# Fan_12V_LED.net
KiCad netlist of a schematic drawn in EasyEDA Pro
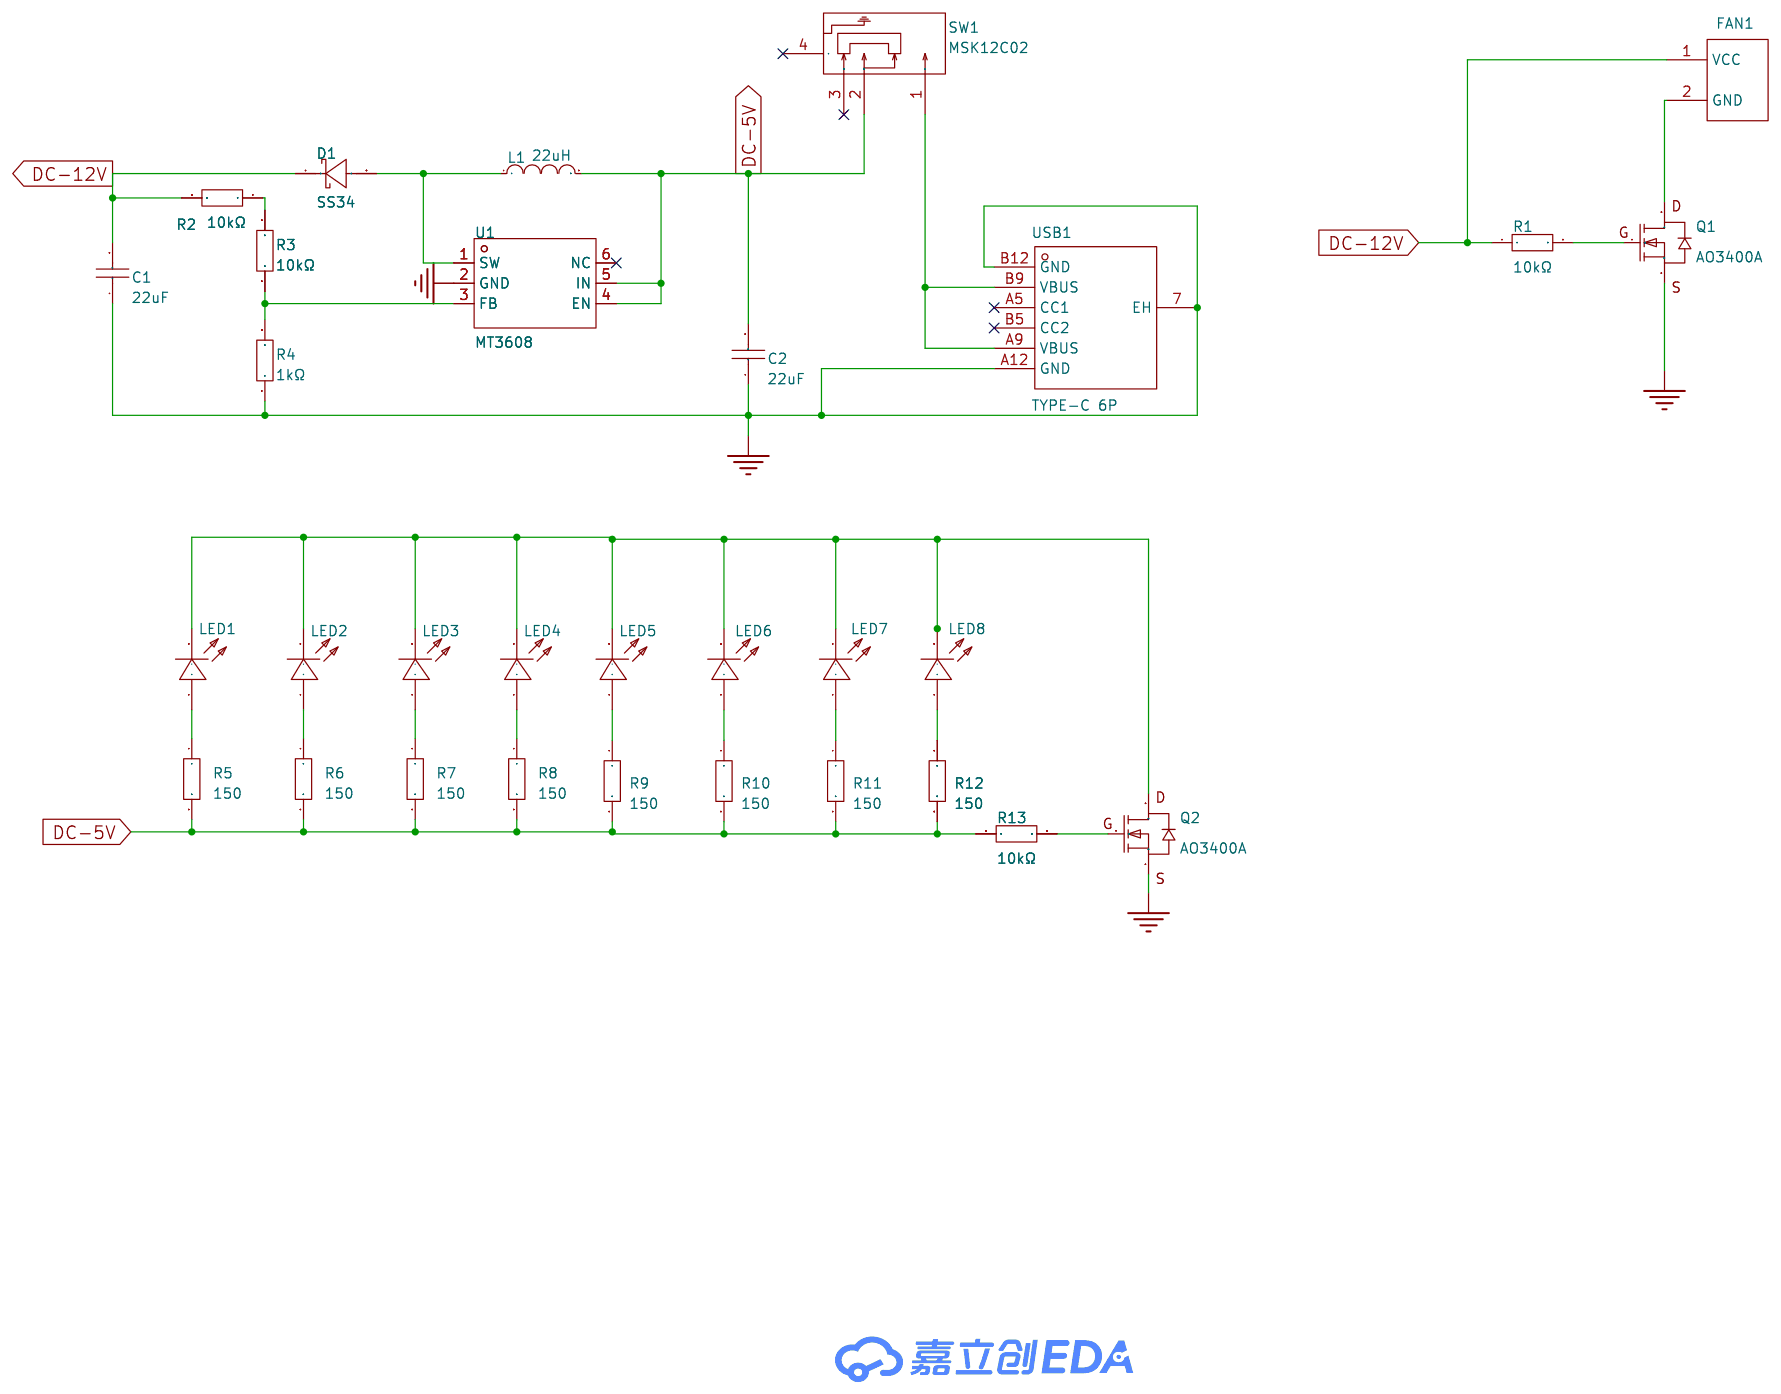
[diagram p0: schematic sheet]

(export (version "E")
  (design (tool "Eeschema 10.0.6"))
  (components
    (comp (ref "C1")
      (value "22uF")
      (footprint "easyedapro:C0603")
      (description "容值:22uF;精度:±20%;额定电压:6.3V;材质(温度系数):X5R;")
      (fields
        (field (name "Manufacturer Part") "CC0603MRX5R5BB226")
        (field (name "Manufacturer") "YAGEO(国巨)")
      )
      (libsource (lib "easyedapro") (part "CC0603MRX5R5BB226"))
    )
    (comp (ref "C2")
      (value "22uF")
      (footprint "easyedapro:C0603")
      (description "容值:22uF;精度:±20%;额定电压:6.3V;材质(温度系数):X5R;")
      (fields
        (field (name "Manufacturer Part") "CC0603MRX5R5BB226")
        (field (name "Manufacturer") "YAGEO(国巨)")
      )
      (libsource (lib "easyedapro") (part "CC0603MRX5R5BB226"))
    )
    (comp (ref "D1")
      (value "SS34")
      (footprint "easyedapro:SMA_L4.2-W2.7-LS5.0-RD")
      (description "二极管配置:-;正向压降(Vf):550mV@3A;直流反向耐压(Vr):40V;整流电流:3A;")
      (fields (field (name "Manufacturer") "JSMSEMI(杰盛微)"))
      (libsource (lib "easyedapro") (part "SS34_C2837271"))
    )
    (comp (ref "FAN1")
      (value "~")
      (footprint "easyedapro:锂电池焊盘封装")
      (libsource (lib "easyedapro") (part "锂电池焊盘"))
    )
    (comp (ref "L1")
      (value "22uH")
      (footprint "easyedapro:IND-SMD_L7.0-W6.6_FXL0630")
      (description "电感值:22uH;精度:±20%;额定电流:2.5A;饱和电流(Isat):3A;类型:一体成型电感;")
      (fields (field (name "Manufacturer Part") "FXL0630-220-M") (field (name "Manufacturer") "cjiang(长江微电)"))
      (libsource (lib "easyedapro") (part "FXL0630-220-M"))
    )
    (comp (ref "LED1")
      (value "NCD0805R1")
      (footprint "easyedapro:LED0805-R-RD")
      (fields (field (name "Manufacturer") "国星光电"))
      (libsource (lib "easyedapro") (part "FC-2012HRK-620D"))
    )
    (comp (ref "LED2")
      (value "NCD0805R1")
      (footprint "easyedapro:LED0805-R-RD")
      (fields (field (name "Manufacturer") "国星光电"))
      (libsource (lib "easyedapro") (part "FC-2012HRK-620D"))
    )
    (comp (ref "LED3")
      (value "NCD0805R1")
      (footprint "easyedapro:LED0805-R-RD")
      (fields (field (name "Manufacturer") "国星光电"))
      (libsource (lib "easyedapro") (part "FC-2012HRK-620D"))
    )
    (comp (ref "LED4")
      (value "NCD0805R1")
      (footprint "easyedapro:LED0805-R-RD")
      (fields (field (name "Manufacturer") "国星光电"))
      (libsource (lib "easyedapro") (part "FC-2012HRK-620D"))
    )
    (comp (ref "LED5")
      (value "NCD0805R1")
      (footprint "easyedapro:LED0805-R-RD")
      (fields (field (name "Manufacturer") "国星光电"))
      (libsource (lib "easyedapro") (part "FC-2012HRK-620D"))
    )
    (comp (ref "LED6")
      (value "NCD0805R1")
      (footprint "easyedapro:LED0805-R-RD")
      (fields (field (name "Manufacturer") "国星光电"))
      (libsource (lib "easyedapro") (part "FC-2012HRK-620D"))
    )
    (comp (ref "LED7")
      (value "NCD0805R1")
      (footprint "easyedapro:LED0805-R-RD")
      (fields (field (name "Manufacturer") "国星光电"))
      (libsource (lib "easyedapro") (part "FC-2012HRK-620D"))
    )
    (comp (ref "LED8")
      (value "NCD0805R1")
      (footprint "easyedapro:LED0805-R-RD")
      (fields (field (name "Manufacturer") "国星光电"))
      (libsource (lib "easyedapro") (part "FC-2012HRK-620D"))
    )
    (comp (ref "Q1")
      (value "AO3400A")
      (footprint "easyedapro:SOT-23-3_L2.9-W1.3-P1.90-LS2.4-BR")
      (fields (field (name "Manufacturer") "UMW(友台半导体)"))
      (libsource (lib "easyedapro") (part "AO3400A_C347475"))
    )
    (comp (ref "Q2")
      (value "AO3400A")
      (footprint "easyedapro:SOT-23-3_L2.9-W1.3-P1.90-LS2.4-BR")
      (fields (field (name "Manufacturer") "UMW(友台半导体)"))
      (libsource (lib "easyedapro") (part "AO3400A_C347475"))
    )
    (comp (ref "R1")
      (value "10kΩ")
      (footprint "easyedapro:R0603")
      (description "电阻类型:厚膜电阻;阻值:10kΩ;精度:±1%;功率:100mW;最大工作电压:75V;温度系数:±100ppm/°C;")
      (fields (field (name "Manufacturer Part") "RC0603FR-0710KL") (field (name "Manufacturer") "YAGEO(国巨)"))
      (libsource (lib "easyedapro") (part "RC0603FR-0710KL"))
    )
    (comp (ref "R2")
      (value "10kΩ")
      (fields (field (name "Manufacturer Part") "RC0603FR-0710KL") (field (name "Manufacturer") "YAGEO(国巨)"))
      (libsource (lib "easyedapro") (part "RC0603FR-0716KL"))
    )
    (comp (ref "R3")
      (value "10kΩ")
      (fields (field (name "Manufacturer Part") "RC0603FR-0710KL") (field (name "Manufacturer") "YAGEO(国巨)"))
      (libsource (lib "easyedapro") (part "RC0603FR-0716KL"))
    )
    (comp (ref "R4")
      (value "1kΩ")
      (fields (field (name "Manufacturer Part") "RC0603FR-071KL") (field (name "Manufacturer") "YAGEO(国巨)"))
      (libsource (lib "easyedapro") (part "RC0603FR-072K2L"))
    )
    (comp (ref "R5")
      (value "150")
      (footprint "easyedapro:R0603")
      (description "电阻类型:厚膜电阻;阻值:100kΩ;精度:±1%;功率:100mW;最大工作电压:75V;温度系数:±100ppm/°C;")
      (fields
        (field (name "Manufacturer Part") "0603WAF1003T5E")
        (field (name "Manufacturer") "UNI-ROYAL(厚声)")
      )
      (libsource (lib "easyedapro") (part "0603WAF1003T5E"))
    )
    (comp (ref "R6")
      (value "150")
      (footprint "easyedapro:R0603")
      (description "电阻类型:厚膜电阻;阻值:100kΩ;精度:±1%;功率:100mW;最大工作电压:75V;温度系数:±100ppm/°C;")
      (fields
        (field (name "Manufacturer Part") "0603WAF1003T5E")
        (field (name "Manufacturer") "UNI-ROYAL(厚声)")
      )
      (libsource (lib "easyedapro") (part "0603WAF1003T5E"))
    )
    (comp (ref "R7")
      (value "150")
      (footprint "easyedapro:R0603")
      (description "电阻类型:厚膜电阻;阻值:100kΩ;精度:±1%;功率:100mW;最大工作电压:75V;温度系数:±100ppm/°C;")
      (fields
        (field (name "Manufacturer Part") "0603WAF1003T5E")
        (field (name "Manufacturer") "UNI-ROYAL(厚声)")
      )
      (libsource (lib "easyedapro") (part "0603WAF1003T5E"))
    )
    (comp (ref "R8")
      (value "150")
      (footprint "easyedapro:R0603")
      (description "电阻类型:厚膜电阻;阻值:100kΩ;精度:±1%;功率:100mW;最大工作电压:75V;温度系数:±100ppm/°C;")
      (fields
        (field (name "Manufacturer Part") "0603WAF1003T5E")
        (field (name "Manufacturer") "UNI-ROYAL(厚声)")
      )
      (libsource (lib "easyedapro") (part "0603WAF1003T5E"))
    )
    (comp (ref "R9")
      (value "150")
      (footprint "easyedapro:R0603")
      (description "电阻类型:厚膜电阻;阻值:100kΩ;精度:±1%;功率:100mW;最大工作电压:75V;温度系数:±100ppm/°C;")
      (fields
        (field (name "Manufacturer Part") "0603WAF1003T5E")
        (field (name "Manufacturer") "UNI-ROYAL(厚声)")
      )
      (libsource (lib "easyedapro") (part "0603WAF1003T5E"))
    )
    (comp (ref "R10")
      (value "150")
      (footprint "easyedapro:R0603")
      (description "电阻类型:厚膜电阻;阻值:100kΩ;精度:±1%;功率:100mW;最大工作电压:75V;温度系数:±100ppm/°C;")
      (fields
        (field (name "Manufacturer Part") "0603WAF1003T5E")
        (field (name "Manufacturer") "UNI-ROYAL(厚声)")
      )
      (libsource (lib "easyedapro") (part "0603WAF1003T5E"))
    )
    (comp (ref "R11")
      (value "150")
      (footprint "easyedapro:R0603")
      (description "电阻类型:厚膜电阻;阻值:100kΩ;精度:±1%;功率:100mW;最大工作电压:75V;温度系数:±100ppm/°C;")
      (fields
        (field (name "Manufacturer Part") "0603WAF1003T5E")
        (field (name "Manufacturer") "UNI-ROYAL(厚声)")
      )
      (libsource (lib "easyedapro") (part "0603WAF1003T5E"))
    )
    (comp (ref "R12")
      (value "150")
      (footprint "easyedapro:R0603")
      (description "电阻类型:厚膜电阻;阻值:100kΩ;精度:±1%;功率:100mW;最大工作电压:75V;温度系数:±100ppm/°C;")
      (fields
        (field (name "Manufacturer Part") "0603WAF1003T5E")
        (field (name "Manufacturer") "UNI-ROYAL(厚声)")
      )
      (libsource (lib "easyedapro") (part "0603WAF1003T5E"))
    )
    (comp (ref "R13")
      (value "10kΩ")
      (footprint "easyedapro:R0603")
      (description "电阻类型:厚膜电阻;阻值:10kΩ;精度:±1%;功率:100mW;最大工作电压:75V;温度系数:±100ppm/°C;")
      (fields (field (name "Manufacturer Part") "RC0603FR-0710KL") (field (name "Manufacturer") "YAGEO(国巨)"))
      (libsource (lib "easyedapro") (part "RC0603FR-0710KL"))
    )
    (comp (ref "SW1")
      (value "MSK12C02")
      (footprint "easyedapro:SW-TH_MSK12C02")
      (description "电路结构:单刀双掷;安装方式:卧贴;开关颜色:-;额定电流(DC):50mA;额定电压(DC):12V;额定电流(AC):-;额定电压(AC):-;机械寿命:1万次;")
      (fields (field (name "Manufacturer") "SHOU HAN(首韩)"))
      (libsource (lib "easyedapro") (part "MSK12C02"))
    )
    (comp (ref "U1")
      (value "MT3608")
      (footprint "easyedapro:SOT-23-6_L2.9-W1.6-P0.95-LS2.8-BL")
      (description "功能类型:升压型;输出类型:可调;工作电压:2V~24V;输出电压:28V;输出电流:2A;")
      (fields (field (name "Manufacturer") "西安航天民芯"))
      (libsource (lib "easyedapro") (part "MT3608"))
    )
    (comp (ref "USB1")
      (value "TYPE-C 6P")
      (footprint "easyedapro:TYPE-C-SMD_TYPE-C-6P")
      (description "连接器类型:Type-C;标准:USB 3.1;公母:母;安装方式:卧贴;触点数量:6P;端口数量:1;额定电流 - 电源:5A;工作温度范围:-40°C~+85°C;")
      (fields (field (name "Manufacturer") "SHOU HAN(首韩)"))
      (libsource (lib "easyedapro") (part "TYPE-C 6P"))
    )
  )
  (nets
    (net (code "1") (name "DC-5V") (class "Default")
      (node (ref "C2") (pin "2") (pinfunction "2_2") (pintype "input"))
      (node (ref "L1") (pin "2") (pinfunction "2_2") (pintype "unspecified"))
      (node (ref "R10") (pin "2") (pinfunction "2_2") (pintype "input"))
      (node (ref "R11") (pin "2") (pinfunction "2_2") (pintype "input"))
      (node (ref "R12") (pin "2") (pinfunction "2_2") (pintype "input"))
      (node (ref "R13") (pin "1") (pinfunction "1_1") (pintype "input"))
      (node (ref "R5") (pin "2") (pinfunction "2_2") (pintype "input"))
      (node (ref "R6") (pin "2") (pinfunction "2_2") (pintype "input"))
      (node (ref "R7") (pin "2") (pinfunction "2_2") (pintype "input"))
      (node (ref "R8") (pin "2") (pinfunction "2_2") (pintype "input"))
      (node (ref "R9") (pin "2") (pinfunction "2_2") (pintype "input"))
      (node (ref "SW1") (pin "2") (pinfunction "2_2") (pintype "unspecified"))
      (node (ref "U1") (pin "4") (pinfunction "EN_4") (pintype "unspecified"))
      (node (ref "U1") (pin "5") (pinfunction "IN_5") (pintype "unspecified"))
    )
    (net (code "2") (name "DC-12V") (class "Default")
      (node (ref "C1") (pin "2") (pinfunction "2_2") (pintype "input"))
      (node (ref "D1") (pin "1") (pinfunction "K_1") (pintype "unspecified"))
      (node (ref "FAN1") (pin "1") (pinfunction "VCC_1") (pintype "input"))
      (node (ref "R1") (pin "1") (pinfunction "1_1") (pintype "input"))
      (node (ref "R2") (pin "2") (pinfunction "2_2") (pintype "input"))
    )
    (net (code "3") (name "GND") (class "Default")
      (node (ref "C1") (pin "1") (pinfunction "1_1") (pintype "input"))
      (node (ref "C2") (pin "1") (pinfunction "1_1") (pintype "input"))
      (node (ref "Q1") (pin "2") (pinfunction "S_2") (pintype "unspecified"))
      (node (ref "Q2") (pin "2") (pinfunction "S_2") (pintype "unspecified"))
      (node (ref "R4") (pin "1") (pinfunction "1_1") (pintype "input"))
      (node (ref "U1") (pin "2") (pinfunction "GND_2") (pintype "unspecified"))
      (node (ref "USB1") (pin "7") (pinfunction "EH_7") (pintype "unspecified"))
      (node (ref "USB1") (pin "A12") (pinfunction "GND_A12") (pintype "unspecified"))
      (node (ref "USB1") (pin "B12") (pinfunction "GND_B12") (pintype "unspecified"))
    )
    (net (code "4") (name "Net-(D1-A)") (class "Default")
      (node (ref "D1") (pin "2") (pinfunction "A_2") (pintype "unspecified"))
      (node (ref "L1") (pin "1") (pinfunction "1_1") (pintype "unspecified"))
      (node (ref "U1") (pin "1") (pinfunction "SW_1") (pintype "unspecified"))
    )
    (net (code "5") (name "Net-(FAN1-GND)") (class "Default")
      (node (ref "FAN1") (pin "2") (pinfunction "GND_2") (pintype "input"))
      (node (ref "Q1") (pin "3") (pinfunction "D_3") (pintype "unspecified"))
    )
    (net (code "6") (name "Net-(LED1-+)") (class "Default")
      (node (ref "LED1") (pin "1") (pinfunction "+_1") (pintype "unspecified"))
      (node (ref "R5") (pin "1") (pinfunction "1_1") (pintype "input"))
    )
    (net (code "7") (name "Net-(LED1--)") (class "Default")
      (node (ref "LED1") (pin "2") (pinfunction "-_2") (pintype "unspecified"))
      (node (ref "LED2") (pin "2") (pinfunction "-_2") (pintype "unspecified"))
      (node (ref "LED3") (pin "2") (pinfunction "-_2") (pintype "unspecified"))
      (node (ref "LED4") (pin "2") (pinfunction "-_2") (pintype "unspecified"))
      (node (ref "LED5") (pin "2") (pinfunction "-_2") (pintype "unspecified"))
      (node (ref "LED6") (pin "2") (pinfunction "-_2") (pintype "unspecified"))
      (node (ref "LED7") (pin "2") (pinfunction "-_2") (pintype "unspecified"))
      (node (ref "LED8") (pin "2") (pinfunction "-_2") (pintype "unspecified"))
      (node (ref "Q2") (pin "3") (pinfunction "D_3") (pintype "unspecified"))
    )
    (net (code "8") (name "Net-(LED2-+)") (class "Default")
      (node (ref "LED2") (pin "1") (pinfunction "+_1") (pintype "unspecified"))
      (node (ref "R6") (pin "1") (pinfunction "1_1") (pintype "input"))
    )
    (net (code "9") (name "Net-(LED3-+)") (class "Default")
      (node (ref "LED3") (pin "1") (pinfunction "+_1") (pintype "unspecified"))
      (node (ref "R7") (pin "1") (pinfunction "1_1") (pintype "input"))
    )
    (net (code "10") (name "Net-(LED4-+)") (class "Default")
      (node (ref "LED4") (pin "1") (pinfunction "+_1") (pintype "unspecified"))
      (node (ref "R8") (pin "1") (pinfunction "1_1") (pintype "input"))
    )
    (net (code "11") (name "Net-(LED5-+)") (class "Default")
      (node (ref "LED5") (pin "1") (pinfunction "+_1") (pintype "unspecified"))
      (node (ref "R9") (pin "1") (pinfunction "1_1") (pintype "input"))
    )
    (net (code "12") (name "Net-(LED6-+)") (class "Default")
      (node (ref "LED6") (pin "1") (pinfunction "+_1") (pintype "unspecified"))
      (node (ref "R10") (pin "1") (pinfunction "1_1") (pintype "input"))
    )
    (net (code "13") (name "Net-(LED7-+)") (class "Default")
      (node (ref "LED7") (pin "1") (pinfunction "+_1") (pintype "unspecified"))
      (node (ref "R11") (pin "1") (pinfunction "1_1") (pintype "input"))
    )
    (net (code "14") (name "Net-(LED8-+)") (class "Default")
      (node (ref "LED8") (pin "1") (pinfunction "+_1") (pintype "unspecified"))
      (node (ref "R12") (pin "1") (pinfunction "1_1") (pintype "input"))
    )
    (net (code "15") (name "Net-(Q1-G)") (class "Default")
      (node (ref "Q1") (pin "1") (pinfunction "G_1") (pintype "unspecified"))
      (node (ref "R1") (pin "2") (pinfunction "2_2") (pintype "input"))
    )
    (net (code "16") (name "Net-(Q2-G)") (class "Default")
      (node (ref "Q2") (pin "1") (pinfunction "G_1") (pintype "unspecified"))
      (node (ref "R13") (pin "2") (pinfunction "2_2") (pintype "input"))
    )
    (net (code "17") (name "Net-(R2-Pad1)") (class "Default")
      (node (ref "R2") (pin "1") (pinfunction "1_1") (pintype "input"))
      (node (ref "R3") (pin "2") (pinfunction "2_2") (pintype "input"))
    )
    (net (code "18") (name "Net-(SW1-Pad1)") (class "Default")
      (node (ref "SW1") (pin "1") (pinfunction "1_1") (pintype "unspecified"))
      (node (ref "USB1") (pin "A9") (pinfunction "VBUS_A9") (pintype "unspecified"))
      (node (ref "USB1") (pin "B9") (pinfunction "VBUS_B9") (pintype "unspecified"))
    )
    (net (code "19") (name "Net-(U1-FB)") (class "Default")
      (node (ref "R3") (pin "1") (pinfunction "1_1") (pintype "input"))
      (node (ref "R4") (pin "2") (pinfunction "2_2") (pintype "input"))
      (node (ref "U1") (pin "3") (pinfunction "FB_3") (pintype "unspecified"))
    )
    (net (code "20") (name "unconnected-(SW1-Pad3)") (class "Default")
      (node (ref "SW1") (pin "3") (pinfunction "3_3") (pintype "unspecified+no_connect"))
    )
    (net (code "21") (name "unconnected-(SW1-Pad4)") (class "Default")
      (node (ref "SW1") (pin "4") (pinfunction "4_4") (pintype "unspecified+no_connect"))
    )
    (net (code "22") (name "unconnected-(U1-NC-Pad6)") (class "Default")
      (node (ref "U1") (pin "6") (pinfunction "NC_6") (pintype "unspecified+no_connect"))
    )
    (net (code "23") (name "unconnected-(USB1-CC1-PadA5)") (class "Default")
      (node (ref "USB1") (pin "A5") (pinfunction "CC1_A5") (pintype "unspecified+no_connect"))
    )
    (net (code "24") (name "unconnected-(USB1-CC2-PadB5)") (class "Default")
      (node (ref "USB1") (pin "B5") (pinfunction "CC2_B5") (pintype "unspecified+no_connect"))
    )
  )
)
